# MCU_peripheral.net
KiCad netlist of a schematic drawn in Altium Designer
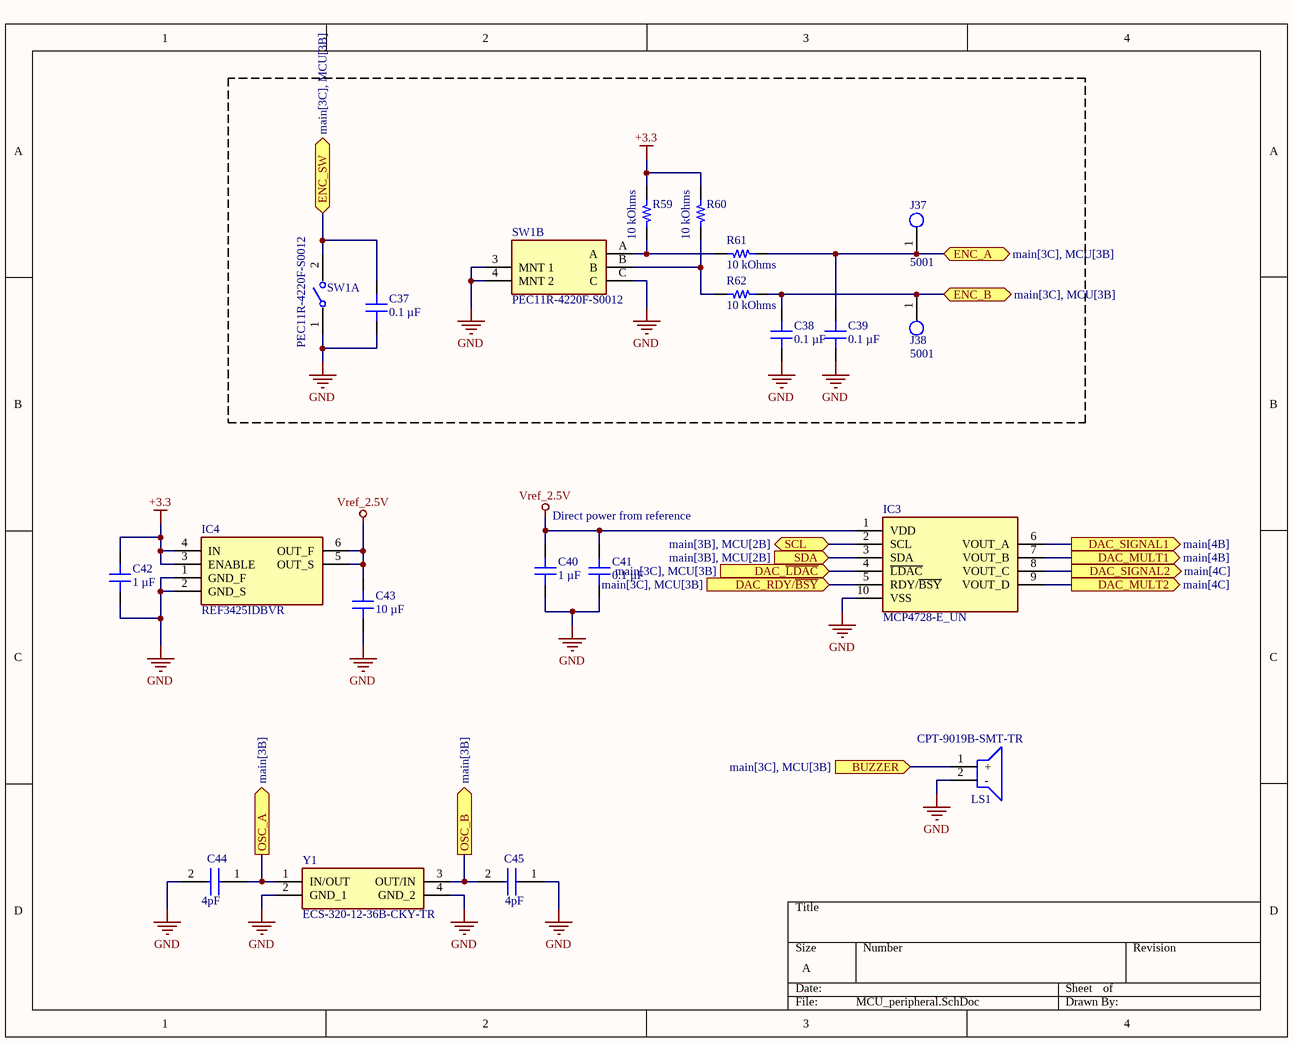
[diagram p0: MCU_peripheral.SchDoc]

(export (version "E")
  (design (tool "Eeschema 10.0.6"))
  (components
    (comp (ref "C37")
      (value "0.1 µF")
      (footprint "CAP 1206_3216 - 0.8MM")
      (description "CAP CER 0.1UF 50V X7R 1206")
      (fields
        (field (name "PART NUMBER") "885012208087")
        (field (name "CAPACITANCE") "0.1 µF")
        (field (name "MANUFACTURER") "Würth Elektronik")
      )
      (libsource (lib "Celestial Altium Library - altium_library") (part "Capacitor"))
    )
    (comp (ref "C38")
      (value "0.1 µF")
      (footprint "CAP 1206_3216 - 0.8MM")
      (description "CAP CER 0.1UF 50V X7R 1206")
      (fields
        (field (name "PART NUMBER") "885012208087")
        (field (name "CAPACITANCE") "0.1 µF")
        (field (name "MANUFACTURER") "Würth Elektronik")
      )
      (libsource (lib "Celestial Altium Library - altium_library") (part "Capacitor"))
    )
    (comp (ref "C39")
      (value "0.1 µF")
      (footprint "CAP 1206_3216 - 0.8MM")
      (description "CAP CER 0.1UF 50V X7R 1206")
      (fields
        (field (name "PART NUMBER") "885012208087")
        (field (name "CAPACITANCE") "0.1 µF")
        (field (name "MANUFACTURER") "Würth Elektronik")
      )
      (libsource (lib "Celestial Altium Library - altium_library") (part "Capacitor"))
    )
    (comp (ref "C40")
      (value "1 µF")
      (footprint "CAP 1206_3216 - 0.8MM")
      (description "CAP CER 1UF 50V X7R 1206")
      (fields
        (field (name "PART NUMBER") "885012208093")
        (field (name "CAPACITANCE") "1 µF")
        (field (name "MANUFACTURER") "Würth Elektronik")
      )
      (libsource (lib "Celestial Altium Library - altium_library") (part "Capacitor"))
    )
    (comp (ref "C41")
      (value "0.1 µF")
      (footprint "CAP 1206_3216 - 0.8MM")
      (description "CAP CER 0.1UF 50V X7R 1206")
      (fields
        (field (name "PART NUMBER") "885012208087")
        (field (name "CAPACITANCE") "0.1 µF")
        (field (name "MANUFACTURER") "Würth Elektronik")
      )
      (libsource (lib "Celestial Altium Library - altium_library") (part "Capacitor"))
    )
    (comp (ref "C42")
      (value "1 µF")
      (footprint "CAP 1206_3216 - 0.8MM")
      (description "CAP CER 1UF 50V X7R 1206")
      (fields
        (field (name "PART NUMBER") "885012208093")
        (field (name "CAPACITANCE") "1 µF")
        (field (name "MANUFACTURER") "Würth Elektronik")
      )
      (libsource (lib "Celestial Altium Library - altium_library") (part "Capacitor"))
    )
    (comp (ref "C43")
      (value "10 µF")
      (footprint "CAP 1206_3216 - 0.8MM")
      (description "CAP CER 10UF 25V X7R 1206")
      (fields
        (field (name "PART NUMBER") "885012208069")
        (field (name "CAPACITANCE") "10 µF")
        (field (name "MANUFACTURER") "Würth Elektronik")
      )
      (libsource (lib "Celestial Altium Library - altium_library") (part "Capacitor"))
    )
    (comp (ref "C44")
      (value "4pF")
      (footprint "CAPC1608X80N")
      (description "Capacitor")
      (fields (field (name "MANUFACTURER_PART_NUMBER") "C1608C0G1H040C080AA"))
      (libsource (lib "za_koncar") (part "C1608C0G1H040C080AA"))
    )
    (comp (ref "C45")
      (value "4pF")
      (footprint "CAPC1608X80N")
      (description "Capacitor")
      (fields (field (name "MANUFACTURER_PART_NUMBER") "C1608C0G1H040C080AA"))
      (libsource (lib "za_koncar") (part "C1608C0G1H040C080AA"))
    )
    (comp (ref "IC3")
      (value "MCP4728-E_UN")
      (footprint "SOP50P490X110-10N")
      (description "Integrated Circuit")
      (fields
        (field (name "MANUFACTURER_PART_NUMBER") "MCP4728-E/UN")
        (field (name "MOUSER PART NUMBER") "579-MCP4728-E/UN")
      )
      (libsource (lib "za_koncar") (part "MCP4728-E_UN"))
    )
    (comp (ref "IC4")
      (value "REF3425IDBVR")
      (footprint "SOT95P280X145-6N")
      (description "Integrated Circuit")
      (fields (field (name "MOUSER PART NUMBER") "595-REF3425IDBVR"))
      (libsource (lib "za_koncar") (part "REF3425IDBVR"))
    )
    (comp (ref "J37")
      (value "5001")
      (footprint "FP-5001-MFG")
      (description "PC TEST POINT MINIATURE BLACK")
      (libsource (lib "za_koncar") (part "CMP-2000-05181-2"))
    )
    (comp (ref "J38")
      (value "5001")
      (footprint "FP-5001-MFG")
      (description "PC TEST POINT MINIATURE BLACK")
      (libsource (lib "za_koncar") (part "CMP-2000-05181-2"))
    )
    (comp (ref "LS1")
      (value "CPT-9019B-SMT-TR")
      (footprint "CPT9019BSMTTR")
      (description "Loudspeaker or Buzzer")
      (fields (field (name "MOUSER PART NUMBER") "179-CPT-9019B-SMT-TR"))
      (libsource (lib "za_koncar") (part "CPT-9019B-SMT-TR"))
    )
    (comp (ref "R59")
      (value "10 kOhms")
      (footprint "YAGEO RES 1206_3216")
      (description "RES SMD 10K OHM 1% 1/4W 1206")
      (fields (field (name "PART NUMBER") "RT1206FRE0710KL") (field (name "MANUFACTURER") "Yageo"))
      (libsource (lib "Celestial Altium Library - altium_library") (part "Resistor"))
    )
    (comp (ref "R60")
      (value "10 kOhms")
      (footprint "YAGEO RES 1206_3216")
      (description "RES SMD 10K OHM 1% 1/4W 1206")
      (fields (field (name "PART NUMBER") "RT1206FRE0710KL") (field (name "MANUFACTURER") "Yageo"))
      (libsource (lib "Celestial Altium Library - altium_library") (part "Resistor"))
    )
    (comp (ref "R61")
      (value "10 kOhms")
      (footprint "YAGEO RES 1206_3216")
      (description "RES SMD 10K OHM 1% 1/4W 1206")
      (fields (field (name "PART NUMBER") "RT1206FRE0710KL") (field (name "MANUFACTURER") "Yageo"))
      (libsource (lib "Celestial Altium Library - altium_library") (part "Resistor"))
    )
    (comp (ref "R62")
      (value "10 kOhms")
      (footprint "YAGEO RES 1206_3216")
      (description "RES SMD 10K OHM 1% 1/4W 1206")
      (fields (field (name "PART NUMBER") "RT1206FRE0710KL") (field (name "MANUFACTURER") "Yageo"))
      (libsource (lib "Celestial Altium Library - altium_library") (part "Resistor"))
    )
    (comp (ref "SW1")
      (value "PEC11R-4220F-S0012")
      (footprint "FP-PEC11R-4220F-S0012-MFG")
      (description "ROTARY ENCODER MECHANICAL 12PPR")
      (libsource (lib "") (part "PEC11R-4220F-S0012_1"))
    )
    (comp (ref "Y1")
      (value "ECS-320-12-36B-CKY-TR")
      (footprint "ECS240836QAESTR")
      (description "Crystal or Oscillator")
      (fields (field (name "MOUSER PART NUMBER") "520-320-12-36B-CKYT"))
      (libsource (lib "za_koncar") (part "ECS-320-12-36B-CKY-TR"))
    )
  )
  (nets
    (net (code "1") (name "+3.3") (class "Default")
      (node (ref "C42") (pin "2") (pinfunction "2_2") (pintype "passive"))
      (node (ref "IC4") (pin "3") (pinfunction "ENABLE_3") (pintype "passive"))
      (node (ref "IC4") (pin "4") (pinfunction "IN_4") (pintype "passive"))
      (node (ref "R59") (pin "1") (pinfunction "1_1") (pintype "passive"))
      (node (ref "R60") (pin "1") (pinfunction "1_1") (pintype "passive"))
    )
    (net (code "2") (name "/BUZZER") (class "Default")
      (node (ref "LS1") (pin "1") (pinfunction "+_1") (pintype "passive"))
    )
    (net (code "3") (name "/DAC_MULT1") (class "Default")
      (node (ref "IC3") (pin "7") (pinfunction "VOUT_B_7") (pintype "passive"))
    )
    (net (code "4") (name "/DAC_MULT2") (class "Default")
      (node (ref "IC3") (pin "9") (pinfunction "VOUT_D_9") (pintype "passive"))
    )
    (net (code "5") (name "/DAC_RDY{slash}~{BSY}") (class "Default")
      (node (ref "IC3") (pin "5") (pinfunction "RDY/~{BSY}_5") (pintype "passive"))
    )
    (net (code "6") (name "/DAC_SIGNAL1") (class "Default")
      (node (ref "IC3") (pin "6") (pinfunction "VOUT_A_6") (pintype "passive"))
    )
    (net (code "7") (name "/DAC_SIGNAL2") (class "Default")
      (node (ref "IC3") (pin "8") (pinfunction "VOUT_C_8") (pintype "passive"))
    )
    (net (code "8") (name "/DAC_~{LDAC}") (class "Default")
      (node (ref "IC3") (pin "4") (pinfunction "~{LDAC}_4") (pintype "passive"))
    )
    (net (code "9") (name "/ENC_A") (class "Default")
      (node (ref "C39") (pin "2") (pinfunction "2_2") (pintype "passive"))
      (node (ref "J37") (pin "1") (pinfunction "1_1") (pintype "passive"))
      (node (ref "R61") (pin "2") (pinfunction "2_2") (pintype "passive"))
    )
    (net (code "10") (name "/ENC_B") (class "Default")
      (node (ref "C38") (pin "2") (pinfunction "2_2") (pintype "passive"))
      (node (ref "J38") (pin "1") (pinfunction "1_1") (pintype "passive"))
      (node (ref "R62") (pin "2") (pinfunction "2_2") (pintype "passive"))
    )
    (net (code "11") (name "/ENC_SW") (class "Default")
      (node (ref "C37") (pin "2") (pinfunction "2_2") (pintype "passive"))
      (node (ref "SW1") (pin "2") (pinfunction "2_2") (pintype "passive"))
    )
    (net (code "12") (name "/OSC_A") (class "Default")
      (node (ref "C44") (pin "1") (pinfunction "1_1") (pintype "passive"))
      (node (ref "Y1") (pin "1") (pinfunction "IN/OUT_1") (pintype "passive"))
    )
    (net (code "13") (name "/OSC_B") (class "Default")
      (node (ref "C45") (pin "2") (pinfunction "2_2") (pintype "passive"))
      (node (ref "Y1") (pin "3") (pinfunction "OUT/IN_3") (pintype "passive"))
    )
    (net (code "14") (name "/SCL") (class "Default")
      (node (ref "IC3") (pin "2") (pinfunction "SCL_2") (pintype "passive"))
    )
    (net (code "15") (name "/SDA") (class "Default")
      (node (ref "IC3") (pin "3") (pinfunction "SDA_3") (pintype "passive"))
    )
    (net (code "16") (name "GND") (class "Default")
      (node (ref "C37") (pin "1") (pinfunction "1_1") (pintype "passive"))
      (node (ref "C38") (pin "1") (pinfunction "1_1") (pintype "passive"))
      (node (ref "C39") (pin "1") (pinfunction "1_1") (pintype "passive"))
      (node (ref "C40") (pin "1") (pinfunction "1_1") (pintype "passive"))
      (node (ref "C41") (pin "1") (pinfunction "1_1") (pintype "passive"))
      (node (ref "C42") (pin "1") (pinfunction "1_1") (pintype "passive"))
      (node (ref "C43") (pin "1") (pinfunction "1_1") (pintype "passive"))
      (node (ref "C44") (pin "2") (pinfunction "2_2") (pintype "passive"))
      (node (ref "C45") (pin "1") (pinfunction "1_1") (pintype "passive"))
      (node (ref "IC3") (pin "10") (pinfunction "VSS_10") (pintype "passive"))
      (node (ref "IC4") (pin "1") (pinfunction "GND_F_1") (pintype "passive"))
      (node (ref "IC4") (pin "2") (pinfunction "GND_S_2") (pintype "passive"))
      (node (ref "LS1") (pin "2") (pinfunction "-_2") (pintype "passive"))
      (node (ref "SW1") (pin "1") (pinfunction "1_1") (pintype "passive"))
      (node (ref "SW1") (pin "3") (pinfunction "MNT_1_3") (pintype "passive"))
      (node (ref "SW1") (pin "4") (pinfunction "MNT_2_4") (pintype "passive"))
      (node (ref "SW1") (pin "C") (pinfunction "C_C") (pintype "passive"))
      (node (ref "Y1") (pin "2") (pinfunction "GND_1_2") (pintype "passive"))
      (node (ref "Y1") (pin "4") (pinfunction "GND_2_4") (pintype "passive"))
    )
    (net (code "17") (name "Net-(R59-Pad2)") (class "Default")
      (node (ref "R59") (pin "2") (pinfunction "2_2") (pintype "passive"))
      (node (ref "R61") (pin "1") (pinfunction "1_1") (pintype "passive"))
      (node (ref "SW1") (pin "A") (pinfunction "A_A") (pintype "passive"))
    )
    (net (code "18") (name "Net-(R60-Pad2)") (class "Default")
      (node (ref "R60") (pin "2") (pinfunction "2_2") (pintype "passive"))
      (node (ref "R62") (pin "1") (pinfunction "1_1") (pintype "passive"))
      (node (ref "SW1") (pin "B") (pinfunction "B_B") (pintype "passive"))
    )
    (net (code "19") (name "Vref_2.5V") (class "Default")
      (node (ref "C40") (pin "2") (pinfunction "2_2") (pintype "passive"))
      (node (ref "C41") (pin "2") (pinfunction "2_2") (pintype "passive"))
      (node (ref "C43") (pin "2") (pinfunction "2_2") (pintype "passive"))
      (node (ref "IC3") (pin "1") (pinfunction "VDD_1") (pintype "passive"))
      (node (ref "IC4") (pin "5") (pinfunction "OUT_S_5") (pintype "passive"))
      (node (ref "IC4") (pin "6") (pinfunction "OUT_F_6") (pintype "passive"))
    )
  )
)
